# as14120.net
KiCad netlist of a schematic drawn in Altium Designer
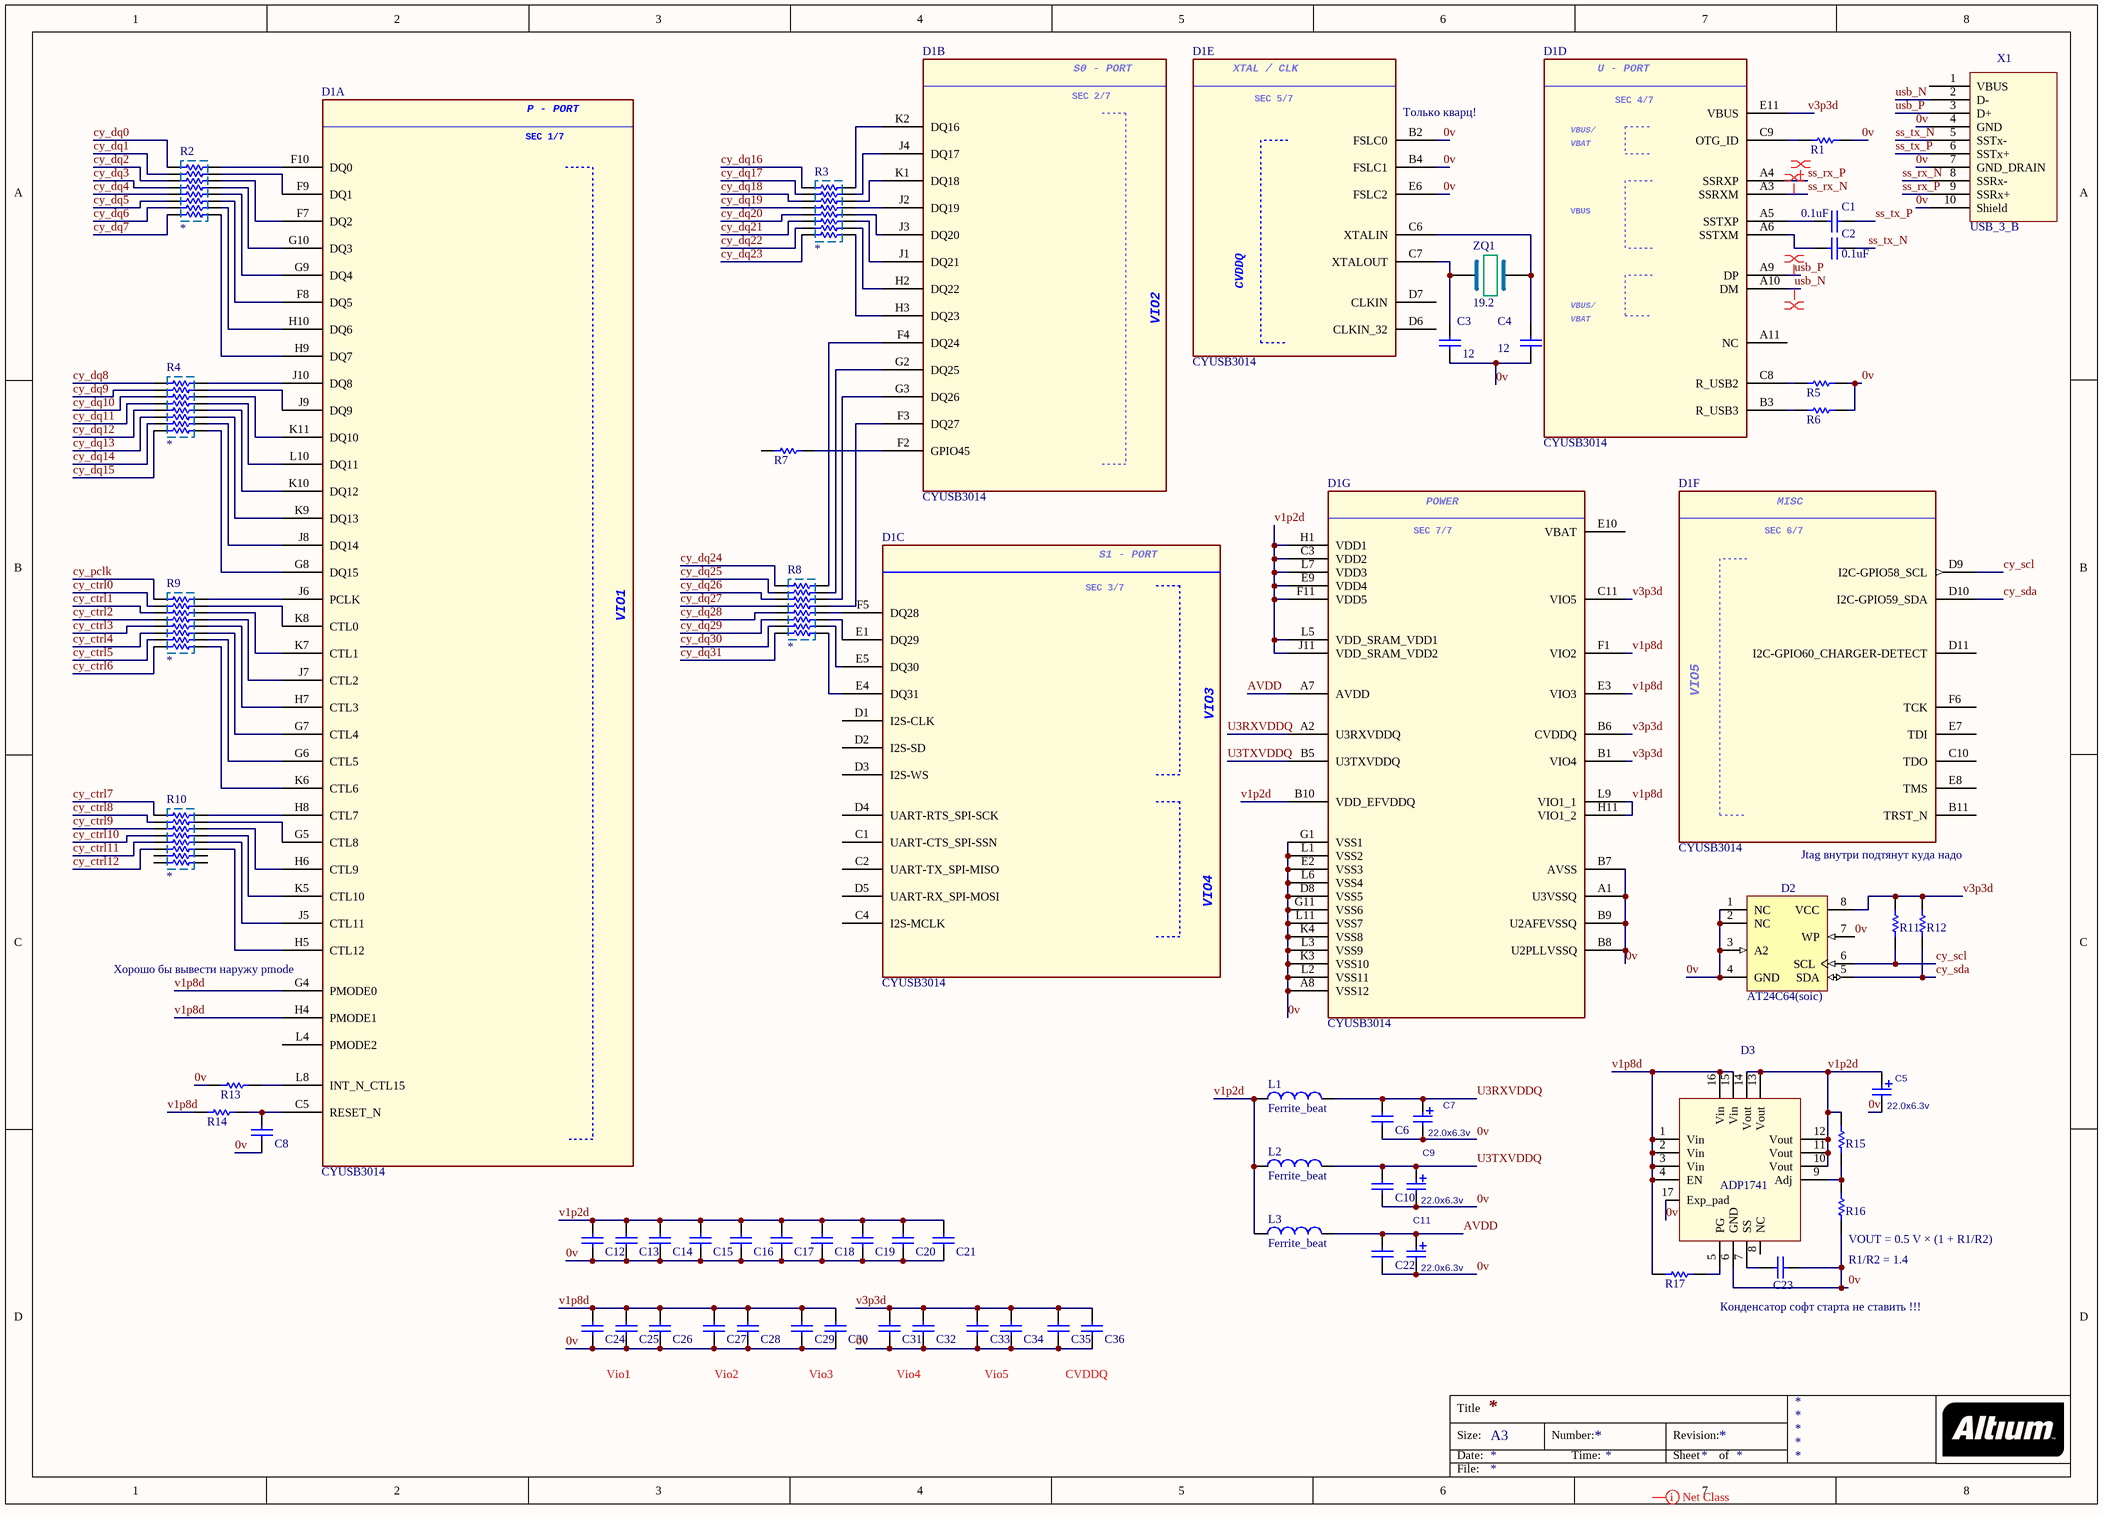
[diagram p0: as14120.SchDoc]

(export (version "E")
  (design (tool "Eeschema 10.0.6"))
  (components
    (comp (ref "C1")
      (value "0.1uF")
      (footprint "CAPC0402(1005)60_M")
      (description "CAP 1uF 10V ±20% 0402 (1005 Metric) Thickness 0.6mm SMD")
      (fields (field (name "TOLERANCE") "±20%") (field (name "Comment") "CAP 1uF 10V 0402(1005)"))
      (libsource (lib "as14120") (part "CAP_0402"))
    )
    (comp (ref "C2")
      (value "0.1uF")
      (footprint "CAPC0402(1005)60_M")
      (description "CAP 1uF 10V ±20% 0402 (1005 Metric) Thickness 0.6mm SMD")
      (fields (field (name "TOLERANCE") "±20%") (field (name "Comment") "CAP 1uF 10V 0402(1005)"))
      (libsource (lib "as14120") (part "CAP_0402"))
    )
    (comp (ref "C3")
      (value "12")
      (footprint "CAPC0805(2012)100_N")
      (fields (field (name "Comment") "CAP_0805"))
      (libsource (lib "as14120") (part "CAP_0805"))
    )
    (comp (ref "C4")
      (value "12")
      (footprint "CAPC0805(2012)100_N")
      (fields (field (name "Comment") "CAP_0805"))
      (libsource (lib "as14120") (part "CAP_0805"))
    )
    (comp (ref "C5")
      (value "22.0x6.3v")
      (footprint "AVX_B")
      (description "AVX_B")
      (libsource (lib "alexsb") (part "AVX_B"))
    )
    (comp (ref "C6")
      (value "CAP 1uF 10V 0402(1005)")
      (footprint "CAPC0402(1005)60_M")
      (description "CAP 1uF 10V ±20% 0402 (1005 Metric) Thickness 0.6mm SMD")
      (fields (field (name "TOLERANCE") "±20%"))
      (libsource (lib "as14120") (part "CAP_0402"))
    )
    (comp (ref "C7")
      (value "22.0x6.3v")
      (footprint "AVX_B")
      (description "AVX_B")
      (libsource (lib "alexsb") (part "AVX_B"))
    )
    (comp (ref "C8")
      (value "CAP 1uF 10V 0402(1005)")
      (footprint "CAPC0402(1005)60_M")
      (description "CAP 1uF 10V ±20% 0402 (1005 Metric) Thickness 0.6mm SMD")
      (fields (field (name "TOLERANCE") "±20%"))
      (libsource (lib "as14120") (part "CAP_0402"))
    )
    (comp (ref "C9")
      (value "22.0x6.3v")
      (footprint "AVX_B")
      (description "AVX_B")
      (libsource (lib "alexsb") (part "AVX_B"))
    )
    (comp (ref "C10")
      (value "CAP 1uF 10V 0402(1005)")
      (footprint "CAPC0402(1005)60_M")
      (description "CAP 1uF 10V ±20% 0402 (1005 Metric) Thickness 0.6mm SMD")
      (fields (field (name "TOLERANCE") "±20%"))
      (libsource (lib "as14120") (part "CAP_0402"))
    )
    (comp (ref "C11")
      (value "22.0x6.3v")
      (footprint "AVX_B")
      (description "AVX_B")
      (libsource (lib "alexsb") (part "AVX_B"))
    )
    (comp (ref "C12")
      (value "CAP 1uF 10V 0402(1005)")
      (footprint "CAPC0402(1005)60_M")
      (description "CAP 1uF 10V ±20% 0402 (1005 Metric) Thickness 0.6mm SMD")
      (fields (field (name "TOLERANCE") "±20%"))
      (libsource (lib "as14120") (part "CAP_0402"))
    )
    (comp (ref "C13")
      (value "CAP 1uF 10V 0402(1005)")
      (footprint "CAPC0402(1005)60_M")
      (description "CAP 1uF 10V ±20% 0402 (1005 Metric) Thickness 0.6mm SMD")
      (fields (field (name "TOLERANCE") "±20%"))
      (libsource (lib "as14120") (part "CAP_0402"))
    )
    (comp (ref "C14")
      (value "CAP 1uF 10V 0402(1005)")
      (footprint "CAPC0402(1005)60_M")
      (description "CAP 1uF 10V ±20% 0402 (1005 Metric) Thickness 0.6mm SMD")
      (fields (field (name "TOLERANCE") "±20%"))
      (libsource (lib "as14120") (part "CAP_0402"))
    )
    (comp (ref "C15")
      (value "CAP 1uF 10V 0402(1005)")
      (footprint "CAPC0402(1005)60_M")
      (description "CAP 1uF 10V ±20% 0402 (1005 Metric) Thickness 0.6mm SMD")
      (fields (field (name "TOLERANCE") "±20%"))
      (libsource (lib "as14120") (part "CAP_0402"))
    )
    (comp (ref "C16")
      (value "CAP 1uF 10V 0402(1005)")
      (footprint "CAPC0402(1005)60_M")
      (description "CAP 1uF 10V ±20% 0402 (1005 Metric) Thickness 0.6mm SMD")
      (fields (field (name "TOLERANCE") "±20%"))
      (libsource (lib "as14120") (part "CAP_0402"))
    )
    (comp (ref "C17")
      (value "CAP 1uF 10V 0402(1005)")
      (footprint "CAPC0402(1005)60_M")
      (description "CAP 1uF 10V ±20% 0402 (1005 Metric) Thickness 0.6mm SMD")
      (fields (field (name "TOLERANCE") "±20%"))
      (libsource (lib "as14120") (part "CAP_0402"))
    )
    (comp (ref "C18")
      (value "CAP 1uF 10V 0402(1005)")
      (footprint "CAPC0402(1005)60_M")
      (description "CAP 1uF 10V ±20% 0402 (1005 Metric) Thickness 0.6mm SMD")
      (fields (field (name "TOLERANCE") "±20%"))
      (libsource (lib "as14120") (part "CAP_0402"))
    )
    (comp (ref "C19")
      (value "CAP 1uF 10V 0402(1005)")
      (footprint "CAPC0402(1005)60_M")
      (description "CAP 1uF 10V ±20% 0402 (1005 Metric) Thickness 0.6mm SMD")
      (fields (field (name "TOLERANCE") "±20%"))
      (libsource (lib "as14120") (part "CAP_0402"))
    )
    (comp (ref "C20")
      (value "CAP 1uF 10V 0402(1005)")
      (footprint "CAPC0402(1005)60_M")
      (description "CAP 1uF 10V ±20% 0402 (1005 Metric) Thickness 0.6mm SMD")
      (fields (field (name "TOLERANCE") "±20%"))
      (libsource (lib "as14120") (part "CAP_0402"))
    )
    (comp (ref "C21")
      (value "CAP 1uF 10V 0402(1005)")
      (footprint "CAPC0402(1005)60_M")
      (description "CAP 1uF 10V ±20% 0402 (1005 Metric) Thickness 0.6mm SMD")
      (fields (field (name "TOLERANCE") "±20%"))
      (libsource (lib "as14120") (part "CAP_0402"))
    )
    (comp (ref "C22")
      (value "CAP 1uF 10V 0402(1005)")
      (footprint "CAPC0402(1005)60_M")
      (description "CAP 1uF 10V ±20% 0402 (1005 Metric) Thickness 0.6mm SMD")
      (fields (field (name "TOLERANCE") "±20%"))
      (libsource (lib "as14120") (part "CAP_0402"))
    )
    (comp (ref "C23")
      (value "CAP 1uF 10V 0402(1005)")
      (footprint "CAPC0402(1005)60_M")
      (description "CAP 1uF 10V ±20% 0402 (1005 Metric) Thickness 0.6mm SMD")
      (fields (field (name "TOLERANCE") "±20%"))
      (libsource (lib "as14120") (part "CAP_0402"))
    )
    (comp (ref "C24")
      (value "CAP 1uF 10V 0402(1005)")
      (footprint "CAPC0402(1005)60_M")
      (description "CAP 1uF 10V ±20% 0402 (1005 Metric) Thickness 0.6mm SMD")
      (fields (field (name "TOLERANCE") "±20%"))
      (libsource (lib "as14120") (part "CAP_0402"))
    )
    (comp (ref "C25")
      (value "CAP 1uF 10V 0402(1005)")
      (footprint "CAPC0402(1005)60_M")
      (description "CAP 1uF 10V ±20% 0402 (1005 Metric) Thickness 0.6mm SMD")
      (fields (field (name "TOLERANCE") "±20%"))
      (libsource (lib "as14120") (part "CAP_0402"))
    )
    (comp (ref "C26")
      (value "CAP 1uF 10V 0402(1005)")
      (footprint "CAPC0402(1005)60_M")
      (description "CAP 1uF 10V ±20% 0402 (1005 Metric) Thickness 0.6mm SMD")
      (fields (field (name "TOLERANCE") "±20%"))
      (libsource (lib "as14120") (part "CAP_0402"))
    )
    (comp (ref "C27")
      (value "CAP 1uF 10V 0402(1005)")
      (footprint "CAPC0402(1005)60_M")
      (description "CAP 1uF 10V ±20% 0402 (1005 Metric) Thickness 0.6mm SMD")
      (fields (field (name "TOLERANCE") "±20%"))
      (libsource (lib "as14120") (part "CAP_0402"))
    )
    (comp (ref "C28")
      (value "CAP 1uF 10V 0402(1005)")
      (footprint "CAPC0402(1005)60_M")
      (description "CAP 1uF 10V ±20% 0402 (1005 Metric) Thickness 0.6mm SMD")
      (fields (field (name "TOLERANCE") "±20%"))
      (libsource (lib "as14120") (part "CAP_0402"))
    )
    (comp (ref "C29")
      (value "CAP 1uF 10V 0402(1005)")
      (footprint "CAPC0402(1005)60_M")
      (description "CAP 1uF 10V ±20% 0402 (1005 Metric) Thickness 0.6mm SMD")
      (fields (field (name "TOLERANCE") "±20%"))
      (libsource (lib "as14120") (part "CAP_0402"))
    )
    (comp (ref "C30")
      (value "CAP 1uF 10V 0402(1005)")
      (footprint "CAPC0402(1005)60_M")
      (description "CAP 1uF 10V ±20% 0402 (1005 Metric) Thickness 0.6mm SMD")
      (fields (field (name "TOLERANCE") "±20%"))
      (libsource (lib "as14120") (part "CAP_0402"))
    )
    (comp (ref "C31")
      (value "CAP 1uF 10V 0402(1005)")
      (footprint "CAPC0402(1005)60_M")
      (description "CAP 1uF 10V ±20% 0402 (1005 Metric) Thickness 0.6mm SMD")
      (fields (field (name "TOLERANCE") "±20%"))
      (libsource (lib "as14120") (part "CAP_0402"))
    )
    (comp (ref "C32")
      (value "CAP 1uF 10V 0402(1005)")
      (footprint "CAPC0402(1005)60_M")
      (description "CAP 1uF 10V ±20% 0402 (1005 Metric) Thickness 0.6mm SMD")
      (fields (field (name "TOLERANCE") "±20%"))
      (libsource (lib "as14120") (part "CAP_0402"))
    )
    (comp (ref "C33")
      (value "CAP 1uF 10V 0402(1005)")
      (footprint "CAPC0402(1005)60_M")
      (description "CAP 1uF 10V ±20% 0402 (1005 Metric) Thickness 0.6mm SMD")
      (fields (field (name "TOLERANCE") "±20%"))
      (libsource (lib "as14120") (part "CAP_0402"))
    )
    (comp (ref "C34")
      (value "CAP 1uF 10V 0402(1005)")
      (footprint "CAPC0402(1005)60_M")
      (description "CAP 1uF 10V ±20% 0402 (1005 Metric) Thickness 0.6mm SMD")
      (fields (field (name "TOLERANCE") "±20%"))
      (libsource (lib "as14120") (part "CAP_0402"))
    )
    (comp (ref "C35")
      (value "CAP 1uF 10V 0402(1005)")
      (footprint "CAPC0402(1005)60_M")
      (description "CAP 1uF 10V ±20% 0402 (1005 Metric) Thickness 0.6mm SMD")
      (fields (field (name "TOLERANCE") "±20%"))
      (libsource (lib "as14120") (part "CAP_0402"))
    )
    (comp (ref "C36")
      (value "CAP 1uF 10V 0402(1005)")
      (footprint "CAPC0402(1005)60_M")
      (description "CAP 1uF 10V ±20% 0402 (1005 Metric) Thickness 0.6mm SMD")
      (fields (field (name "TOLERANCE") "±20%"))
      (libsource (lib "as14120") (part "CAP_0402"))
    )
    (comp (ref "D1")
      (value "CYUSB3014")
      (footprint "BGA121C80P11X11")
      (libsource (lib "as14120") (part "CYUSB3014-BZXC"))
    )
    (comp (ref "D2")
      (value "AT24C64(soic)")
      (footprint "8S1_N")
      (libsource (lib "Atmel Serial EEPROM") (part "AT24C08BN-SP25-T"))
    )
    (comp (ref "D3") (value "ADP1741") (footprint "CP-16-4_N") (libsource (lib "as14120") (part "ADP1741")))
    (comp (ref "L1")
      (value "Ferrite_beat")
      (footprint "CAPC0805(2012)100_N")
      (libsource (lib "as14120") (part "Ferrite_beat"))
    )
    (comp (ref "L2")
      (value "Ferrite_beat")
      (footprint "CAPC0805(2012)100_N")
      (libsource (lib "as14120") (part "Ferrite_beat"))
    )
    (comp (ref "L3")
      (value "Ferrite_beat")
      (footprint "CAPC0805(2012)100_N")
      (libsource (lib "as14120") (part "Ferrite_beat"))
    )
    (comp (ref "R1")
      (value "1K 5% 0603(1608)")
      (footprint "RESC0603(1608)_L")
      (description "1K 0.1W 5% 0603 (1608 Metric)  SMD")
      (fields (field (name "TOLERANCE") "5 %") (field (name "POWER") "0.1 W"))
      (libsource (lib "as14120") (part "RES_0603"))
    )
    (comp (ref "R2") (value "*") (footprint "cay16-j8") (libsource (lib "as14120") (part "cay16-j8")))
    (comp (ref "R3") (value "*") (footprint "cay16-j8") (libsource (lib "as14120") (part "cay16-j8")))
    (comp (ref "R4") (value "*") (footprint "cay16-j8") (libsource (lib "as14120") (part "cay16-j8")))
    (comp (ref "R5")
      (value "1K 1% 0805(2012)")
      (footprint "RESC0805(2012)_L")
      (description "1K 0.125W 1% 0805 (2012 Metric)  SMD")
      (fields (field (name "TOLERANCE") "1 %") (field (name "POWER") "0.125 W"))
      (libsource (lib "as14120") (part "RES_0805"))
    )
    (comp (ref "R6")
      (value "1K 1% 0805(2012)")
      (footprint "RESC0805(2012)_L")
      (description "1K 0.125W 1% 0805 (2012 Metric)  SMD")
      (fields (field (name "TOLERANCE") "1 %") (field (name "POWER") "0.125 W"))
      (libsource (lib "as14120") (part "RES_0805"))
    )
    (comp (ref "R7")
      (value "1K 5% 0603(1608)")
      (footprint "RESC0603(1608)_L")
      (description "1K 0.1W 5% 0603 (1608 Metric)  SMD")
      (fields (field (name "TOLERANCE") "5 %") (field (name "POWER") "0.1 W"))
      (libsource (lib "as14120") (part "RES_0603"))
    )
    (comp (ref "R8") (value "*") (footprint "cay16-j8") (libsource (lib "as14120") (part "cay16-j8")))
    (comp (ref "R9") (value "*") (footprint "cay16-j8") (libsource (lib "as14120") (part "cay16-j8")))
    (comp (ref "R10") (value "*") (footprint "cay16-j8") (libsource (lib "as14120") (part "cay16-j8")))
    (comp (ref "R11")
      (value "1K 5% 0603(1608)")
      (footprint "RESC0603(1608)_L")
      (description "1K 0.1W 5% 0603 (1608 Metric)  SMD")
      (fields (field (name "TOLERANCE") "5 %") (field (name "POWER") "0.1 W"))
      (libsource (lib "as14120") (part "RES_0603"))
    )
    (comp (ref "R12")
      (value "1K 5% 0603(1608)")
      (footprint "RESC0603(1608)_L")
      (description "1K 0.1W 5% 0603 (1608 Metric)  SMD")
      (fields (field (name "TOLERANCE") "5 %") (field (name "POWER") "0.1 W"))
      (libsource (lib "as14120") (part "RES_0603"))
    )
    (comp (ref "R13")
      (value "1K 5% 0603(1608)")
      (footprint "RESC0603(1608)_L")
      (description "1K 0.1W 5% 0603 (1608 Metric)  SMD")
      (fields (field (name "TOLERANCE") "5 %") (field (name "POWER") "0.1 W"))
      (libsource (lib "as14120") (part "RES_0603"))
    )
    (comp (ref "R14")
      (value "1K 5% 0603(1608)")
      (footprint "RESC0603(1608)_L")
      (description "1K 0.1W 5% 0603 (1608 Metric)  SMD")
      (fields (field (name "TOLERANCE") "5 %") (field (name "POWER") "0.1 W"))
      (libsource (lib "as14120") (part "RES_0603"))
    )
    (comp (ref "R15")
      (value "1K 1% 0805(2012)")
      (footprint "RESC0805(2012)_L")
      (description "1K 0.125W 1% 0805 (2012 Metric)  SMD")
      (fields (field (name "TOLERANCE") "1 %") (field (name "POWER") "0.125 W"))
      (libsource (lib "as14120") (part "RES_0805"))
    )
    (comp (ref "R16")
      (value "1K 1% 0805(2012)")
      (footprint "RESC0805(2012)_L")
      (description "1K 0.125W 1% 0805 (2012 Metric)  SMD")
      (fields (field (name "TOLERANCE") "1 %") (field (name "POWER") "0.125 W"))
      (libsource (lib "as14120") (part "RES_0805"))
    )
    (comp (ref "R17")
      (value "1K 5% 0603(1608)")
      (footprint "RESC0603(1608)_L")
      (description "1K 0.1W 5% 0603 (1608 Metric)  SMD")
      (fields (field (name "TOLERANCE") "5 %") (field (name "POWER") "0.1 W"))
      (libsource (lib "as14120") (part "RES_0603"))
    )
    (comp (ref "X1") (value "USB_3_B") (footprint "USB3_B") (libsource (lib "as14120") (part "USB_3_B")))
    (comp (ref "ZQ1")
      (value "19.2")
      (footprint "BCY-W2/E4.7")
      (fields (field (name "Comment") "Resonator"))
      (libsource (lib "as14120") (part "Resonator"))
    )
  )
  (nets
    (net (code "1") (name "/0v") (class "Default")
      (node (ref "C10") (pin "1") (pinfunction "1_1") (pintype "passive"))
      (node (ref "C11") (pin "2") (pintype "passive"))
      (node (ref "C12") (pin "1") (pinfunction "1_1") (pintype "passive"))
      (node (ref "C13") (pin "1") (pinfunction "1_1") (pintype "passive"))
      (node (ref "C14") (pin "1") (pinfunction "1_1") (pintype "passive"))
      (node (ref "C15") (pin "1") (pinfunction "1_1") (pintype "passive"))
      (node (ref "C16") (pin "1") (pinfunction "1_1") (pintype "passive"))
      (node (ref "C17") (pin "1") (pinfunction "1_1") (pintype "passive"))
      (node (ref "C18") (pin "1") (pinfunction "1_1") (pintype "passive"))
      (node (ref "C19") (pin "1") (pinfunction "1_1") (pintype "passive"))
      (node (ref "C20") (pin "1") (pinfunction "1_1") (pintype "passive"))
      (node (ref "C21") (pin "1") (pinfunction "1_1") (pintype "passive"))
      (node (ref "C22") (pin "1") (pinfunction "1_1") (pintype "passive"))
      (node (ref "C23") (pin "1") (pinfunction "1_1") (pintype "passive"))
      (node (ref "C24") (pin "1") (pinfunction "1_1") (pintype "passive"))
      (node (ref "C25") (pin "1") (pinfunction "1_1") (pintype "passive"))
      (node (ref "C26") (pin "1") (pinfunction "1_1") (pintype "passive"))
      (node (ref "C27") (pin "1") (pinfunction "1_1") (pintype "passive"))
      (node (ref "C28") (pin "1") (pinfunction "1_1") (pintype "passive"))
      (node (ref "C29") (pin "1") (pinfunction "1_1") (pintype "passive"))
      (node (ref "C3") (pin "1") (pinfunction "1_1") (pintype "passive"))
      (node (ref "C30") (pin "1") (pinfunction "1_1") (pintype "passive"))
      (node (ref "C31") (pin "1") (pinfunction "1_1") (pintype "passive"))
      (node (ref "C32") (pin "1") (pinfunction "1_1") (pintype "passive"))
      (node (ref "C33") (pin "1") (pinfunction "1_1") (pintype "passive"))
      (node (ref "C34") (pin "1") (pinfunction "1_1") (pintype "passive"))
      (node (ref "C35") (pin "1") (pinfunction "1_1") (pintype "passive"))
      (node (ref "C36") (pin "1") (pinfunction "1_1") (pintype "passive"))
      (node (ref "C4") (pin "1") (pinfunction "1_1") (pintype "passive"))
      (node (ref "C5") (pin "2") (pintype "passive"))
      (node (ref "C6") (pin "1") (pinfunction "1_1") (pintype "passive"))
      (node (ref "C7") (pin "2") (pintype "passive"))
      (node (ref "C8") (pin "1") (pinfunction "1_1") (pintype "passive"))
      (node (ref "C9") (pin "2") (pintype "passive"))
      (node (ref "D1") (pin "A1") (pinfunction "U3VSSQ_A1") (pintype "passive"))
      (node (ref "D1") (pin "A8") (pinfunction "VSS12_A8") (pintype "passive"))
      (node (ref "D1") (pin "B2") (pinfunction "FSLC0_B2") (pintype "passive"))
      (node (ref "D1") (pin "B4") (pinfunction "FSLC1_B4") (pintype "passive"))
      (node (ref "D1") (pin "B7") (pinfunction "AVSS_B7") (pintype "passive"))
      (node (ref "D1") (pin "B8") (pinfunction "U2PLLVSSQ_B8") (pintype "passive"))
      (node (ref "D1") (pin "B9") (pinfunction "U2AFEVSSQ_B9") (pintype "passive"))
      (node (ref "D1") (pin "D8") (pinfunction "VSS5_D8") (pintype "passive"))
      (node (ref "D1") (pin "E2") (pinfunction "VSS3_E2") (pintype "passive"))
      (node (ref "D1") (pin "E6") (pinfunction "FSLC2_E6") (pintype "passive"))
      (node (ref "D1") (pin "G1") (pinfunction "VSS1_G1") (pintype "passive"))
      (node (ref "D1") (pin "G11") (pinfunction "VSS6_G11") (pintype "passive"))
      (node (ref "D1") (pin "K3") (pinfunction "VSS10_K3") (pintype "passive"))
      (node (ref "D1") (pin "K4") (pinfunction "VSS8_K4") (pintype "passive"))
      (node (ref "D1") (pin "L1") (pinfunction "VSS2_L1") (pintype "passive"))
      (node (ref "D1") (pin "L11") (pinfunction "VSS7_L11") (pintype "passive"))
      (node (ref "D1") (pin "L2") (pinfunction "VSS11_L2") (pintype "passive"))
      (node (ref "D1") (pin "L3") (pinfunction "VSS9_L3") (pintype "passive"))
      (node (ref "D1") (pin "L6") (pinfunction "VSS4_L6") (pintype "passive"))
      (node (ref "D2") (pin "1") (pinfunction "NC_1") (pintype "passive"))
      (node (ref "D2") (pin "2") (pinfunction "NC_2") (pintype "passive"))
      (node (ref "D2") (pin "3") (pinfunction "A2_3") (pintype "input"))
      (node (ref "D2") (pin "4") (pinfunction "GND_4") (pintype "power_in"))
      (node (ref "D2") (pin "7") (pinfunction "WP_7") (pintype "input"))
      (node (ref "D3") (pin "17") (pinfunction "Exp_pad_17") (pintype "passive"))
      (node (ref "D3") (pin "6") (pinfunction "GND_6") (pintype "passive"))
      (node (ref "R1") (pin "2") (pinfunction "2_2") (pintype "passive"))
      (node (ref "R13") (pin "2") (pinfunction "2_2") (pintype "passive"))
      (node (ref "R16") (pin "1") (pinfunction "1_1") (pintype "passive"))
      (node (ref "R5") (pin "2") (pinfunction "2_2") (pintype "passive"))
      (node (ref "R6") (pin "2") (pinfunction "2_2") (pintype "passive"))
      (node (ref "X1") (pin "10") (pinfunction "Shield_10") (pintype "passive"))
      (node (ref "X1") (pin "4") (pinfunction "GND_4") (pintype "passive"))
      (node (ref "X1") (pin "7") (pinfunction "GND_DRAIN_7") (pintype "passive"))
    )
    (net (code "2") (name "/AVDD") (class "Default")
      (node (ref "C11") (pin "1") (pintype "passive"))
      (node (ref "C22") (pin "2") (pinfunction "2_2") (pintype "passive"))
      (node (ref "D1") (pin "A7") (pinfunction "AVDD_A7") (pintype "passive"))
      (node (ref "L3") (pin "2") (pinfunction "2_2") (pintype "passive"))
    )
    (net (code "3") (name "/U3RXVDDQ") (class "Default")
      (node (ref "C6") (pin "2") (pinfunction "2_2") (pintype "passive"))
      (node (ref "C7") (pin "1") (pintype "passive"))
      (node (ref "D1") (pin "A2") (pinfunction "U3RXVDDQ_A2") (pintype "passive"))
      (node (ref "L1") (pin "2") (pinfunction "2_2") (pintype "passive"))
    )
    (net (code "4") (name "/U3TXVDDQ") (class "Default")
      (node (ref "C10") (pin "2") (pinfunction "2_2") (pintype "passive"))
      (node (ref "C9") (pin "1") (pintype "passive"))
      (node (ref "D1") (pin "B5") (pinfunction "U3TXVDDQ_B5") (pintype "passive"))
      (node (ref "L2") (pin "2") (pinfunction "2_2") (pintype "passive"))
    )
    (net (code "5") (name "/cy_ctrl0") (class "Default")
      (node (ref "R9") (pin "3") (pinfunction "3_3") (pintype "passive"))
    )
    (net (code "6") (name "/cy_ctrl1") (class "Default")
      (node (ref "R9") (pin "5") (pinfunction "5_5") (pintype "passive"))
    )
    (net (code "7") (name "/cy_ctrl2") (class "Default")
      (node (ref "R9") (pin "7") (pinfunction "7_7") (pintype "passive"))
    )
    (net (code "8") (name "/cy_ctrl3") (class "Default")
      (node (ref "R9") (pin "9") (pinfunction "9_9") (pintype "passive"))
    )
    (net (code "9") (name "/cy_ctrl4") (class "Default")
      (node (ref "R9") (pin "11") (pinfunction "11_11") (pintype "passive"))
    )
    (net (code "10") (name "/cy_ctrl5") (class "Default")
      (node (ref "R9") (pin "13") (pinfunction "13_13") (pintype "passive"))
    )
    (net (code "11") (name "/cy_ctrl6") (class "Default")
      (node (ref "R9") (pin "15") (pinfunction "15_15") (pintype "passive"))
    )
    (net (code "12") (name "/cy_ctrl7") (class "Default")
      (node (ref "R10") (pin "1") (pinfunction "1_1") (pintype "passive"))
    )
    (net (code "13") (name "/cy_ctrl8") (class "Default")
      (node (ref "R10") (pin "3") (pinfunction "3_3") (pintype "passive"))
    )
    (net (code "14") (name "/cy_ctrl9") (class "Default")
      (node (ref "R10") (pin "5") (pinfunction "5_5") (pintype "passive"))
    )
    (net (code "15") (name "/cy_ctrl10") (class "Default")
      (node (ref "R10") (pin "7") (pinfunction "7_7") (pintype "passive"))
    )
    (net (code "16") (name "/cy_ctrl11") (class "Default")
      (node (ref "R10") (pin "9") (pinfunction "9_9") (pintype "passive"))
    )
    (net (code "17") (name "/cy_ctrl12") (class "Default")
      (node (ref "R10") (pin "11") (pinfunction "11_11") (pintype "passive"))
    )
    (net (code "18") (name "/cy_dq0") (class "Default")
      (node (ref "R2") (pin "1") (pinfunction "1_1") (pintype "passive"))
    )
    (net (code "19") (name "/cy_dq1") (class "Default")
      (node (ref "R2") (pin "3") (pinfunction "3_3") (pintype "passive"))
    )
    (net (code "20") (name "/cy_dq2") (class "Default")
      (node (ref "R2") (pin "5") (pinfunction "5_5") (pintype "passive"))
    )
    (net (code "21") (name "/cy_dq3") (class "Default")
      (node (ref "R2") (pin "7") (pinfunction "7_7") (pintype "passive"))
    )
    (net (code "22") (name "/cy_dq4") (class "Default")
      (node (ref "R2") (pin "9") (pinfunction "9_9") (pintype "passive"))
    )
    (net (code "23") (name "/cy_dq5") (class "Default")
      (node (ref "R2") (pin "11") (pinfunction "11_11") (pintype "passive"))
    )
    (net (code "24") (name "/cy_dq6") (class "Default")
      (node (ref "R2") (pin "13") (pinfunction "13_13") (pintype "passive"))
    )
    (net (code "25") (name "/cy_dq7") (class "Default")
      (node (ref "R2") (pin "15") (pinfunction "15_15") (pintype "passive"))
    )
    (net (code "26") (name "/cy_dq8") (class "Default")
      (node (ref "R4") (pin "1") (pinfunction "1_1") (pintype "passive"))
    )
    (net (code "27") (name "/cy_dq9") (class "Default")
      (node (ref "R4") (pin "3") (pinfunction "3_3") (pintype "passive"))
    )
    (net (code "28") (name "/cy_dq10") (class "Default")
      (node (ref "R4") (pin "5") (pinfunction "5_5") (pintype "passive"))
    )
    (net (code "29") (name "/cy_dq11") (class "Default")
      (node (ref "R4") (pin "7") (pinfunction "7_7") (pintype "passive"))
    )
    (net (code "30") (name "/cy_dq12") (class "Default")
      (node (ref "R4") (pin "9") (pinfunction "9_9") (pintype "passive"))
    )
    (net (code "31") (name "/cy_dq13") (class "Default")
      (node (ref "R4") (pin "11") (pinfunction "11_11") (pintype "passive"))
    )
    (net (code "32") (name "/cy_dq14") (class "Default")
      (node (ref "R4") (pin "13") (pinfunction "13_13") (pintype "passive"))
    )
    (net (code "33") (name "/cy_dq15") (class "Default")
      (node (ref "R4") (pin "15") (pinfunction "15_15") (pintype "passive"))
    )
    (net (code "34") (name "/cy_dq16") (class "Default")
      (node (ref "R3") (pin "1") (pinfunction "1_1") (pintype "passive"))
    )
    (net (code "35") (name "/cy_dq17") (class "Default")
      (node (ref "R3") (pin "3") (pinfunction "3_3") (pintype "passive"))
    )
    (net (code "36") (name "/cy_dq18") (class "Default")
      (node (ref "R3") (pin "5") (pinfunction "5_5") (pintype "passive"))
    )
    (net (code "37") (name "/cy_dq19") (class "Default")
      (node (ref "R3") (pin "7") (pinfunction "7_7") (pintype "passive"))
    )
    (net (code "38") (name "/cy_dq20") (class "Default")
      (node (ref "R3") (pin "9") (pinfunction "9_9") (pintype "passive"))
    )
    (net (code "39") (name "/cy_dq21") (class "Default")
      (node (ref "R3") (pin "11") (pinfunction "11_11") (pintype "passive"))
    )
    (net (code "40") (name "/cy_dq22") (class "Default")
      (node (ref "R3") (pin "13") (pinfunction "13_13") (pintype "passive"))
    )
    (net (code "41") (name "/cy_dq23") (class "Default")
      (node (ref "R3") (pin "15") (pinfunction "15_15") (pintype "passive"))
    )
    (net (code "42") (name "/cy_dq24") (class "Default")
      (node (ref "R8") (pin "1") (pinfunction "1_1") (pintype "passive"))
    )
    (net (code "43") (name "/cy_dq25") (class "Default")
      (node (ref "R8") (pin "3") (pinfunction "3_3") (pintype "passive"))
    )
    (net (code "44") (name "/cy_dq26") (class "Default")
      (node (ref "R8") (pin "5") (pinfunction "5_5") (pintype "passive"))
    )
    (net (code "45") (name "/cy_dq27") (class "Default")
      (node (ref "R8") (pin "7") (pinfunction "7_7") (pintype "passive"))
    )
    (net (code "46") (name "/cy_dq28") (class "Default")
      (node (ref "R8") (pin "9") (pinfunction "9_9") (pintype "passive"))
    )
    (net (code "47") (name "/cy_dq29") (class "Default")
      (node (ref "R8") (pin "11") (pinfunction "11_11") (pintype "passive"))
    )
    (net (code "48") (name "/cy_dq30") (class "Default")
      (node (ref "R8") (pin "13") (pinfunction "13_13") (pintype "passive"))
    )
    (net (code "49") (name "/cy_dq31") (class "Default")
      (node (ref "R8") (pin "15") (pinfunction "15_15") (pintype "passive"))
    )
    (net (code "50") (name "/cy_pclk") (class "Default")
      (node (ref "R9") (pin "1") (pinfunction "1_1") (pintype "passive"))
    )
    (net (code "51") (name "/cy_scl") (class "Default")
      (node (ref "D1") (pin "D9") (pinfunction "I2C-GPIO58_SCL_D9") (pintype "output"))
      (node (ref "D2") (pin "6") (pinfunction "SCL_6") (pintype "input"))
      (node (ref "R11") (pin "1") (pinfunction "1_1") (pintype "passive"))
    )
    (net (code "52") (name "/cy_sda") (class "Default")
      (node (ref "D1") (pin "D10") (pinfunction "I2C-GPIO59_SDA_D10") (pintype "passive"))
      (node (ref "D2") (pin "5") (pinfunction "SDA_5") (pintype "bidirectional"))
      (node (ref "R12") (pin "1") (pinfunction "1_1") (pintype "passive"))
    )
    (net (code "53") (name "/ss_rx_N") (class "Default")
      (node (ref "D1") (pin "A3") (pinfunction "SSRXM_A3") (pintype "passive"))
      (node (ref "X1") (pin "8") (pinfunction "SSRx-_8") (pintype "passive"))
    )
    (net (code "54") (name "/ss_rx_P") (class "Default")
      (node (ref "D1") (pin "A4") (pinfunction "SSRXP_A4") (pintype "passive"))
      (node (ref "X1") (pin "9") (pinfunction "SSRx+_9") (pintype "passive"))
    )
    (net (code "55") (name "/ss_tx_N") (class "Default")
      (node (ref "C2") (pin "1") (pinfunction "1_1") (pintype "passive"))
      (node (ref "X1") (pin "5") (pinfunction "SSTx-_5") (pintype "passive"))
    )
    (net (code "56") (name "/ss_tx_P") (class "Default")
      (node (ref "C1") (pin "1") (pinfunction "1_1") (pintype "passive"))
      (node (ref "X1") (pin "6") (pinfunction "SSTx+_6") (pintype "passive"))
    )
    (net (code "57") (name "/usb_N") (class "Default")
      (node (ref "D1") (pin "A10") (pinfunction "DM_A10") (pintype "passive"))
      (node (ref "X1") (pin "2") (pinfunction "D-_2") (pintype "passive"))
    )
    (net (code "58") (name "/usb_P") (class "Default")
      (node (ref "D1") (pin "A9") (pinfunction "DP_A9") (pintype "passive"))
      (node (ref "X1") (pin "3") (pinfunction "D+_3") (pintype "passive"))
    )
    (net (code "59") (name "/v1p2d") (class "Default")
      (node (ref "C12") (pin "2") (pinfunction "2_2") (pintype "passive"))
      (node (ref "C13") (pin "2") (pinfunction "2_2") (pintype "passive"))
      (node (ref "C14") (pin "2") (pinfunction "2_2") (pintype "passive"))
      (node (ref "C15") (pin "2") (pinfunction "2_2") (pintype "passive"))
      (node (ref "C16") (pin "2") (pinfunction "2_2") (pintype "passive"))
      (node (ref "C17") (pin "2") (pinfunction "2_2") (pintype "passive"))
      (node (ref "C18") (pin "2") (pinfunction "2_2") (pintype "passive"))
      (node (ref "C19") (pin "2") (pinfunction "2_2") (pintype "passive"))
      (node (ref "C20") (pin "2") (pinfunction "2_2") (pintype "passive"))
      (node (ref "C21") (pin "2") (pinfunction "2_2") (pintype "passive"))
      (node (ref "C5") (pin "1") (pintype "passive"))
      (node (ref "D1") (pin "B10") (pinfunction "VDD_EFVDDQ_B10") (pintype "passive"))
      (node (ref "D1") (pin "C3") (pinfunction "VDD2_C3") (pintype "passive"))
      (node (ref "D1") (pin "E9") (pinfunction "VDD4_E9") (pintype "passive"))
      (node (ref "D1") (pin "F11") (pinfunction "VDD5_F11") (pintype "passive"))
      (node (ref "D1") (pin "H1") (pinfunction "VDD1_H1") (pintype "passive"))
      (node (ref "D1") (pin "J11") (pinfunction "VDD_SRAM_VDD2_J11") (pintype "passive"))
      (node (ref "D1") (pin "L5") (pinfunction "VDD_SRAM_VDD1_L5") (pintype "passive"))
      (node (ref "D1") (pin "L7") (pinfunction "VDD3_L7") (pintype "passive"))
      (node (ref "D3") (pin "10") (pinfunction "Vout_10") (pintype "passive"))
      (node (ref "D3") (pin "11") (pinfunction "Vout_11") (pintype "passive"))
      (node (ref "D3") (pin "12") (pinfunction "Vout_12") (pintype "passive"))
      (node (ref "D3") (pin "13") (pinfunction "Vout_13") (pintype "passive"))
      (node (ref "D3") (pin "14") (pinfunction "Vout_14") (pintype "passive"))
      (node (ref "L1") (pin "1") (pinfunction "1_1") (pintype "passive"))
      (node (ref "L2") (pin "1") (pinfunction "1_1") (pintype "passive"))
      (node (ref "L3") (pin "1") (pinfunction "1_1") (pintype "passive"))
      (node (ref "R15") (pin "2") (pinfunction "2_2") (pintype "passive"))
    )
    (net (code "60") (name "/v1p8d") (class "Default")
      (node (ref "C24") (pin "2") (pinfunction "2_2") (pintype "passive"))
      (node (ref "C25") (pin "2") (pinfunction "2_2") (pintype "passive"))
      (node (ref "C26") (pin "2") (pinfunction "2_2") (pintype "passive"))
      (node (ref "C27") (pin "2") (pinfunction "2_2") (pintype "passive"))
      (node (ref "C28") (pin "2") (pinfunction "2_2") (pintype "passive"))
      (node (ref "C29") (pin "2") (pinfunction "2_2") (pintype "passive"))
      (node (ref "C30") (pin "2") (pinfunction "2_2") (pintype "passive"))
      (node (ref "D1") (pin "E3") (pinfunction "VIO3_E3") (pintype "passive"))
      (node (ref "D1") (pin "F1") (pinfunction "VIO2_F1") (pintype "passive"))
      (node (ref "D1") (pin "G4") (pinfunction "PMODE0_G4") (pintype "passive"))
      (node (ref "D1") (pin "H11") (pinfunction "VIO1_2_H11") (pintype "passive"))
      (node (ref "D1") (pin "H4") (pinfunction "PMODE1_H4") (pintype "passive"))
      (node (ref "D1") (pin "L9") (pinfunction "VIO1_1_L9") (pintype "passive"))
      (node (ref "D3") (pin "1") (pinfunction "Vin_1") (pintype "passive"))
      (node (ref "D3") (pin "15") (pinfunction "Vin_15") (pintype "passive"))
      (node (ref "D3") (pin "16") (pinfunction "Vin_16") (pintype "passive"))
      (node (ref "D3") (pin "2") (pinfunction "Vin_2") (pintype "passive"))
      (node (ref "D3") (pin "3") (pinfunction "Vin_3") (pintype "passive"))
      (node (ref "D3") (pin "4") (pinfunction "EN_4") (pintype "passive"))
      (node (ref "R14") (pin "2") (pinfunction "2_2") (pintype "passive"))
      (node (ref "R17") (pin "2") (pinfunction "2_2") (pintype "passive"))
    )
    (net (code "61") (name "/v3p3d") (class "Default")
      (node (ref "C31") (pin "2") (pinfunction "2_2") (pintype "passive"))
      (node (ref "C32") (pin "2") (pinfunction "2_2") (pintype "passive"))
      (node (ref "C33") (pin "2") (pinfunction "2_2") (pintype "passive"))
      (node (ref "C34") (pin "2") (pinfunction "2_2") (pintype "passive"))
      (node (ref "C35") (pin "2") (pinfunction "2_2") (pintype "passive"))
      (node (ref "C36") (pin "2") (pinfunction "2_2") (pintype "passive"))
      (node (ref "D1") (pin "B1") (pinfunction "VIO4_B1") (pintype "passive"))
      (node (ref "D1") (pin "B6") (pinfunction "CVDDQ_B6") (pintype "passive"))
      (node (ref "D1") (pin "C11") (pinfunction "VIO5_C11") (pintype "passive"))
      (node (ref "D1") (pin "E11") (pinfunction "VBUS_E11") (pintype "passive"))
      (node (ref "D2") (pin "8") (pinfunction "VCC_8") (pintype "power_in"))
      (node (ref "R11") (pin "2") (pinfunction "2_2") (pintype "passive"))
      (node (ref "R12") (pin "2") (pinfunction "2_2") (pintype "passive"))
    )
    (net (code "62") (name "Net-(D1A-CTL0)") (class "Default")
      (node (ref "D1") (pin "K8") (pinfunction "CTL0_K8") (pintype "passive"))
      (node (ref "R9") (pin "4") (pinfunction "4_4") (pintype "passive"))
    )
    (net (code "63") (name "Net-(D1A-CTL1)") (class "Default")
      (node (ref "D1") (pin "K7") (pinfunction "CTL1_K7") (pintype "passive"))
      (node (ref "R9") (pin "6") (pinfunction "6_6") (pintype "passive"))
    )
    (net (code "64") (name "Net-(D1A-CTL2)") (class "Default")
      (node (ref "D1") (pin "J7") (pinfunction "CTL2_J7") (pintype "passive"))
      (node (ref "R9") (pin "8") (pinfunction "8_8") (pintype "passive"))
    )
    (net (code "65") (name "Net-(D1A-CTL3)") (class "Default")
      (node (ref "D1") (pin "H7") (pinfunction "CTL3_H7") (pintype "passive"))
      (node (ref "R9") (pin "10") (pinfunction "10_10") (pintype "passive"))
    )
    (net (code "66") (name "Net-(D1A-CTL4)") (class "Default")
      (node (ref "D1") (pin "G7") (pinfunction "CTL4_G7") (pintype "passive"))
      (node (ref "R9") (pin "12") (pinfunction "12_12") (pintype "passive"))
    )
    (net (code "67") (name "Net-(D1A-CTL5)") (class "Default")
      (node (ref "D1") (pin "G6") (pinfunction "CTL5_G6") (pintype "passive"))
      (node (ref "R9") (pin "14") (pinfunction "14_14") (pintype "passive"))
    )
    (net (code "68") (name "Net-(D1A-CTL6)") (class "Default")
      (node (ref "D1") (pin "K6") (pinfunction "CTL6_K6") (pintype "passive"))
      (node (ref "R9") (pin "16") (pinfunction "16_16") (pintype "passive"))
    )
    (net (code "69") (name "Net-(D1A-CTL7)") (class "Default")
      (node (ref "D1") (pin "H8") (pinfunction "CTL7_H8") (pintype "passive"))
      (node (ref "R10") (pin "2") (pinfunction "2_2") (pintype "passive"))
    )
    (net (code "70") (name "Net-(D1A-CTL8)") (class "Default")
      (node (ref "D1") (pin "G5") (pinfunction "CTL8_G5") (pintype "passive"))
      (node (ref "R10") (pin "4") (pinfunction "4_4") (pintype "passive"))
    )
    (net (code "71") (name "Net-(D1A-CTL9)") (class "Default")
      (node (ref "D1") (pin "H6") (pinfunction "CTL9_H6") (pintype "passive"))
      (node (ref "R10") (pin "6") (pinfunction "6_6") (pintype "passive"))
    )
    (net (code "72") (name "Net-(D1A-CTL10)") (class "Default")
      (node (ref "D1") (pin "K5") (pinfunction "CTL10_K5") (pintype "passive"))
      (node (ref "R10") (pin "8") (pinfunction "8_8") (pintype "passive"))
    )
    (net (code "73") (name "Net-(D1A-CTL11)") (class "Default")
      (node (ref "D1") (pin "J5") (pinfunction "CTL11_J5") (pintype "passive"))
      (node (ref "R10") (pin "10") (pinfunction "10_10") (pintype "passive"))
    )
    (net (code "74") (name "Net-(D1A-CTL12)") (class "Default")
      (node (ref "D1") (pin "H5") (pinfunction "CTL12_H5") (pintype "passive"))
      (node (ref "R10") (pin "12") (pinfunction "12_12") (pintype "passive"))
    )
    (net (code "75") (name "Net-(D1A-DQ0)") (class "Default")
      (node (ref "D1") (pin "F10") (pinfunction "DQ0_F10") (pintype "passive"))
      (node (ref "R2") (pin "2") (pinfunction "2_2") (pintype "passive"))
    )
    (net (code "76") (name "Net-(D1A-DQ1)") (class "Default")
      (node (ref "D1") (pin "F9") (pinfunction "DQ1_F9") (pintype "passive"))
      (node (ref "R2") (pin "4") (pinfunction "4_4") (pintype "passive"))
    )
    (net (code "77") (name "Net-(D1A-DQ2)") (class "Default")
      (node (ref "D1") (pin "F7") (pinfunction "DQ2_F7") (pintype "passive"))
      (node (ref "R2") (pin "6") (pinfunction "6_6") (pintype "passive"))
    )
    (net (code "78") (name "Net-(D1A-DQ3)") (class "Default")
      (node (ref "D1") (pin "G10") (pinfunction "DQ3_G10") (pintype "passive"))
      (node (ref "R2") (pin "8") (pinfunction "8_8") (pintype "passive"))
    )
    (net (code "79") (name "Net-(D1A-DQ4)") (class "Default")
      (node (ref "D1") (pin "G9") (pinfunction "DQ4_G9") (pintype "passive"))
      (node (ref "R2") (pin "10") (pinfunction "10_10") (pintype "passive"))
    )
    (net (code "80") (name "Net-(D1A-DQ5)") (class "Default")
      (node (ref "D1") (pin "F8") (pinfunction "DQ5_F8") (pintype "passive"))
      (node (ref "R2") (pin "12") (pinfunction "12_12") (pintype "passive"))
    )
    (net (code "81") (name "Net-(D1A-DQ6)") (class "Default")
      (node (ref "D1") (pin "H10") (pinfunction "DQ6_H10") (pintype "passive"))
      (node (ref "R2") (pin "14") (pinfunction "14_14") (pintype "passive"))
    )
    (net (code "82") (name "Net-(D1A-DQ7)") (class "Default")
      (node (ref "D1") (pin "H9") (pinfunction "DQ7_H9") (pintype "passive"))
      (node (ref "R2") (pin "16") (pinfunction "16_16") (pintype "passive"))
    )
    (net (code "83") (name "Net-(D1A-DQ8)") (class "Default")
      (node (ref "D1") (pin "J10") (pinfunction "DQ8_J10") (pintype "passive"))
      (node (ref "R4") (pin "2") (pinfunction "2_2") (pintype "passive"))
    )
    (net (code "84") (name "Net-(D1A-DQ9)") (class "Default")
      (node (ref "D1") (pin "J9") (pinfunction "DQ9_J9") (pintype "passive"))
      (node (ref "R4") (pin "4") (pinfunction "4_4") (pintype "passive"))
    )
    (net (code "85") (name "Net-(D1A-DQ10)") (class "Default")
      (node (ref "D1") (pin "K11") (pinfunction "DQ10_K11") (pintype "passive"))
      (node (ref "R4") (pin "6") (pinfunction "6_6") (pintype "passive"))
    )
    (net (code "86") (name "Net-(D1A-DQ11)") (class "Default")
      (node (ref "D1") (pin "L10") (pinfunction "DQ11_L10") (pintype "passive"))
      (node (ref "R4") (pin "8") (pinfunction "8_8") (pintype "passive"))
    )
    (net (code "87") (name "Net-(D1A-DQ12)") (class "Default")
      (node (ref "D1") (pin "K10") (pinfunction "DQ12_K10") (pintype "passive"))
      (node (ref "R4") (pin "10") (pinfunction "10_10") (pintype "passive"))
    )
    (net (code "88") (name "Net-(D1A-DQ13)") (class "Default")
      (node (ref "D1") (pin "K9") (pinfunction "DQ13_K9") (pintype "passive"))
      (node (ref "R4") (pin "12") (pinfunction "12_12") (pintype "passive"))
    )
    (net (code "89") (name "Net-(D1A-DQ14)") (class "Default")
      (node (ref "D1") (pin "J8") (pinfunction "DQ14_J8") (pintype "passive"))
      (node (ref "R4") (pin "14") (pinfunction "14_14") (pintype "passive"))
    )
    (net (code "90") (name "Net-(D1A-DQ15)") (class "Default")
      (node (ref "D1") (pin "G8") (pinfunction "DQ15_G8") (pintype "passive"))
      (node (ref "R4") (pin "16") (pinfunction "16_16") (pintype "passive"))
    )
    (net (code "91") (name "Net-(D1A-INT_N_CTL15)") (class "Default")
      (node (ref "D1") (pin "L8") (pinfunction "INT_N_CTL15_L8") (pintype "passive"))
      (node (ref "R13") (pin "1") (pinfunction "1_1") (pintype "passive"))
    )
    (net (code "92") (name "Net-(D1A-PCLK)") (class "Default")
      (node (ref "D1") (pin "J6") (pinfunction "PCLK_J6") (pintype "passive"))
      (node (ref "R9") (pin "2") (pinfunction "2_2") (pintype "passive"))
    )
    (net (code "93") (name "Net-(D1A-RESET_N)") (class "Default")
      (node (ref "C8") (pin "2") (pinfunction "2_2") (pintype "passive"))
      (node (ref "D1") (pin "C5") (pinfunction "RESET_N_C5") (pintype "passive"))
      (node (ref "R14") (pin "1") (pinfunction "1_1") (pintype "passive"))
    )
    (net (code "94") (name "Net-(D1B-DQ16)") (class "Default")
      (node (ref "D1") (pin "K2") (pinfunction "DQ16_K2") (pintype "passive"))
      (node (ref "R3") (pin "2") (pinfunction "2_2") (pintype "passive"))
    )
    (net (code "95") (name "Net-(D1B-DQ17)") (class "Default")
      (node (ref "D1") (pin "J4") (pinfunction "DQ17_J4") (pintype "passive"))
      (node (ref "R3") (pin "4") (pinfunction "4_4") (pintype "passive"))
    )
    (net (code "96") (name "Net-(D1B-DQ18)") (class "Default")
      (node (ref "D1") (pin "K1") (pinfunction "DQ18_K1") (pintype "passive"))
      (node (ref "R3") (pin "6") (pinfunction "6_6") (pintype "passive"))
    )
    (net (code "97") (name "Net-(D1B-DQ19)") (class "Default")
      (node (ref "D1") (pin "J2") (pinfunction "DQ19_J2") (pintype "passive"))
      (node (ref "R3") (pin "8") (pinfunction "8_8") (pintype "passive"))
    )
    (net (code "98") (name "Net-(D1B-DQ20)") (class "Default")
      (node (ref "D1") (pin "J3") (pinfunction "DQ20_J3") (pintype "passive"))
      (node (ref "R3") (pin "10") (pinfunction "10_10") (pintype "passive"))
    )
    (net (code "99") (name "Net-(D1B-DQ21)") (class "Default")
      (node (ref "D1") (pin "J1") (pinfunction "DQ21_J1") (pintype "passive"))
      (node (ref "R3") (pin "12") (pinfunction "12_12") (pintype "passive"))
    )
    (net (code "100") (name "Net-(D1B-DQ22)") (class "Default")
      (node (ref "D1") (pin "H2") (pinfunction "DQ22_H2") (pintype "passive"))
      (node (ref "R3") (pin "14") (pinfunction "14_14") (pintype "passive"))
    )
    (net (code "101") (name "Net-(D1B-DQ23)") (class "Default")
      (node (ref "D1") (pin "H3") (pinfunction "DQ23_H3") (pintype "passive"))
      (node (ref "R3") (pin "16") (pinfunction "16_16") (pintype "passive"))
    )
    (net (code "102") (name "Net-(D1B-DQ24)") (class "Default")
      (node (ref "D1") (pin "F4") (pinfunction "DQ24_F4") (pintype "passive"))
      (node (ref "R8") (pin "2") (pinfunction "2_2") (pintype "passive"))
    )
    (net (code "103") (name "Net-(D1B-DQ25)") (class "Default")
      (node (ref "D1") (pin "G2") (pinfunction "DQ25_G2") (pintype "passive"))
      (node (ref "R8") (pin "4") (pinfunction "4_4") (pintype "passive"))
    )
    (net (code "104") (name "Net-(D1B-DQ26)") (class "Default")
      (node (ref "D1") (pin "G3") (pinfunction "DQ26_G3") (pintype "passive"))
      (node (ref "R8") (pin "6") (pinfunction "6_6") (pintype "passive"))
    )
    (net (code "105") (name "Net-(D1B-DQ27)") (class "Default")
      (node (ref "D1") (pin "F3") (pinfunction "DQ27_F3") (pintype "passive"))
      (node (ref "R8") (pin "8") (pinfunction "8_8") (pintype "passive"))
    )
    (net (code "106") (name "Net-(D1B-GPIO45)") (class "Default")
      (node (ref "D1") (pin "F2") (pinfunction "GPIO45_F2") (pintype "passive"))
      (node (ref "R7") (pin "1") (pinfunction "1_1") (pintype "passive"))
    )
    (net (code "107") (name "Net-(D1C-DQ28)") (class "Default")
      (node (ref "D1") (pin "F5") (pinfunction "DQ28_F5") (pintype "passive"))
      (node (ref "R8") (pin "10") (pinfunction "10_10") (pintype "passive"))
    )
    (net (code "108") (name "Net-(D1C-DQ29)") (class "Default")
      (node (ref "D1") (pin "E1") (pinfunction "DQ29_E1") (pintype "passive"))
      (node (ref "R8") (pin "12") (pinfunction "12_12") (pintype "passive"))
    )
    (net (code "109") (name "Net-(D1C-DQ30)") (class "Default")
      (node (ref "D1") (pin "E5") (pinfunction "DQ30_E5") (pintype "passive"))
      (node (ref "R8") (pin "14") (pinfunction "14_14") (pintype "passive"))
    )
    (net (code "110") (name "Net-(D1C-DQ31)") (class "Default")
      (node (ref "D1") (pin "E4") (pinfunction "DQ31_E4") (pintype "passive"))
      (node (ref "R8") (pin "16") (pinfunction "16_16") (pintype "passive"))
    )
    (net (code "111") (name "Net-(D1D-OTG_ID)") (class "Default")
      (node (ref "D1") (pin "C9") (pinfunction "OTG_ID_C9") (pintype "passive"))
      (node (ref "R1") (pin "1") (pinfunction "1_1") (pintype "passive"))
    )
    (net (code "112") (name "Net-(D1D-R_USB2)") (class "Default")
      (node (ref "D1") (pin "C8") (pinfunction "R_USB2_C8") (pintype "passive"))
      (node (ref "R5") (pin "1") (pinfunction "1_1") (pintype "passive"))
    )
    (net (code "113") (name "Net-(D1D-R_USB3)") (class "Default")
      (node (ref "D1") (pin "B3") (pinfunction "R_USB3_B3") (pintype "passive"))
      (node (ref "R6") (pin "1") (pinfunction "1_1") (pintype "passive"))
    )
    (net (code "114") (name "Net-(D1D-SSTXM)") (class "Default")
      (node (ref "C2") (pin "2") (pinfunction "2_2") (pintype "passive"))
      (node (ref "D1") (pin "A6") (pinfunction "SSTXM_A6") (pintype "passive"))
    )
    (net (code "115") (name "Net-(D1D-SSTXP)") (class "Default")
      (node (ref "C1") (pin "2") (pinfunction "2_2") (pintype "passive"))
      (node (ref "D1") (pin "A5") (pinfunction "SSTXP_A5") (pintype "passive"))
    )
    (net (code "116") (name "Net-(D1E-XTALIN)") (class "Default")
      (node (ref "C4") (pin "2") (pinfunction "2_2") (pintype "passive"))
      (node (ref "D1") (pin "C6") (pinfunction "XTALIN_C6") (pintype "passive"))
      (node (ref "ZQ1") (pin "2") (pinfunction "2_2") (pintype "passive"))
    )
    (net (code "117") (name "Net-(D1E-XTALOUT)") (class "Default")
      (node (ref "C3") (pin "2") (pinfunction "2_2") (pintype "passive"))
      (node (ref "D1") (pin "C7") (pinfunction "XTALOUT_C7") (pintype "passive"))
      (node (ref "ZQ1") (pin "1") (pinfunction "1_1") (pintype "passive"))
    )
    (net (code "118") (name "Net-(D3-Adj)") (class "Default")
      (node (ref "D3") (pin "9") (pinfunction "Adj_9") (pintype "passive"))
      (node (ref "R15") (pin "1") (pinfunction "1_1") (pintype "passive"))
      (node (ref "R16") (pin "2") (pinfunction "2_2") (pintype "passive"))
    )
    (net (code "119") (name "Net-(D3-PG)") (class "Default")
      (node (ref "D3") (pin "5") (pinfunction "PG_5") (pintype "passive"))
      (node (ref "R17") (pin "1") (pinfunction "1_1") (pintype "passive"))
    )
    (net (code "120") (name "Net-(D3-SS)") (class "Default")
      (node (ref "C23") (pin "2") (pinfunction "2_2") (pintype "passive"))
      (node (ref "D3") (pin "7") (pinfunction "SS_7") (pintype "passive"))
    )
    (net (code "121") (name "unconnected-(D1A-PMODE2-PadL4)") (class "Default")
      (node (ref "D1") (pin "L4") (pinfunction "PMODE2_L4") (pintype "passive"))
    )
    (net (code "122") (name "unconnected-(D1C-I2S-CLK-PadD1)") (class "Default")
      (node (ref "D1") (pin "D1") (pinfunction "I2S-CLK_D1") (pintype "passive"))
    )
    (net (code "123") (name "unconnected-(D1C-I2S-MCLK-PadC4)") (class "Default")
      (node (ref "D1") (pin "C4") (pinfunction "I2S-MCLK_C4") (pintype "passive"))
    )
    (net (code "124") (name "unconnected-(D1C-I2S-SD-PadD2)") (class "Default")
      (node (ref "D1") (pin "D2") (pinfunction "I2S-SD_D2") (pintype "passive"))
    )
    (net (code "125") (name "unconnected-(D1C-I2S-WS-PadD3)") (class "Default")
      (node (ref "D1") (pin "D3") (pinfunction "I2S-WS_D3") (pintype "passive"))
    )
    (net (code "126") (name "unconnected-(D1C-UART-CTS_SPI-SSN-PadC1)") (class "Default")
      (node (ref "D1") (pin "C1") (pinfunction "UART-CTS_SPI-SSN_C1") (pintype "passive"))
    )
    (net (code "127") (name "unconnected-(D1C-UART-RTS_SPI-SCK-PadD4)") (class "Default")
      (node (ref "D1") (pin "D4") (pinfunction "UART-RTS_SPI-SCK_D4") (pintype "passive"))
    )
    (net (code "128") (name "unconnected-(D1C-UART-RX_SPI-MOSI-PadD5)") (class "Default")
      (node (ref "D1") (pin "D5") (pinfunction "UART-RX_SPI-MOSI_D5") (pintype "passive"))
    )
    (net (code "129") (name "unconnected-(D1C-UART-TX_SPI-MISO-PadC2)") (class "Default")
      (node (ref "D1") (pin "C2") (pinfunction "UART-TX_SPI-MISO_C2") (pintype "passive"))
    )
    (net (code "130") (name "unconnected-(D1D-NC-PadA11)") (class "Default")
      (node (ref "D1") (pin "A11") (pinfunction "NC_A11") (pintype "passive"))
    )
    (net (code "131") (name "unconnected-(D1E-CLKIN-PadD7)") (class "Default")
      (node (ref "D1") (pin "D7") (pinfunction "CLKIN_D7") (pintype "passive"))
    )
    (net (code "132") (name "unconnected-(D1E-CLKIN_32-PadD6)") (class "Default")
      (node (ref "D1") (pin "D6") (pinfunction "CLKIN_32_D6") (pintype "passive"))
    )
    (net (code "133") (name "unconnected-(D1F-I2C-GPIO60_CHARGER-DETECT-PadD11)") (class "Default")
      (node (ref "D1") (pin "D11") (pinfunction "I2C-GPIO60_CHARGER-DETECT_D11") (pintype "passive"))
    )
    (net (code "134") (name "unconnected-(D1F-TCK-PadF6)") (class "Default")
      (node (ref "D1") (pin "F6") (pinfunction "TCK_F6") (pintype "passive"))
    )
    (net (code "135") (name "unconnected-(D1F-TDI-PadE7)") (class "Default")
      (node (ref "D1") (pin "E7") (pinfunction "TDI_E7") (pintype "passive"))
    )
    (net (code "136") (name "unconnected-(D1F-TDO-PadC10)") (class "Default")
      (node (ref "D1") (pin "C10") (pinfunction "TDO_C10") (pintype "passive"))
    )
    (net (code "137") (name "unconnected-(D1F-TMS-PadE8)") (class "Default")
      (node (ref "D1") (pin "E8") (pinfunction "TMS_E8") (pintype "passive"))
    )
    (net (code "138") (name "unconnected-(D1F-TRST_N-PadB11)") (class "Default")
      (node (ref "D1") (pin "B11") (pinfunction "TRST_N_B11") (pintype "passive"))
    )
    (net (code "139") (name "unconnected-(D1G-VBAT-PadE10)") (class "Default")
      (node (ref "D1") (pin "E10") (pinfunction "VBAT_E10") (pintype "passive"))
    )
    (net (code "140") (name "unconnected-(D3-NC-Pad8)") (class "Default")
      (node (ref "D3") (pin "8") (pinfunction "NC_8") (pintype "passive"))
    )
    (net (code "141") (name "unconnected-(R7-Pad2)") (class "Default")
      (node (ref "R7") (pin "2") (pinfunction "2_2") (pintype "passive"))
    )
    (net (code "142") (name "unconnected-(R10-Pad13)") (class "Default")
      (node (ref "R10") (pin "13") (pinfunction "13_13") (pintype "passive"))
    )
    (net (code "143") (name "unconnected-(R10-Pad14)") (class "Default")
      (node (ref "R10") (pin "14") (pinfunction "14_14") (pintype "passive"))
    )
    (net (code "144") (name "unconnected-(R10-Pad15)") (class "Default")
      (node (ref "R10") (pin "15") (pinfunction "15_15") (pintype "passive"))
    )
    (net (code "145") (name "unconnected-(R10-Pad16)") (class "Default")
      (node (ref "R10") (pin "16") (pinfunction "16_16") (pintype "passive"))
    )
    (net (code "146") (name "unconnected-(X1-VBUS-Pad1)") (class "Default")
      (node (ref "X1") (pin "1") (pinfunction "VBUS_1") (pintype "passive"))
    )
  )
)
